# main.net
KiCad netlist of a schematic drawn in Altium Designer
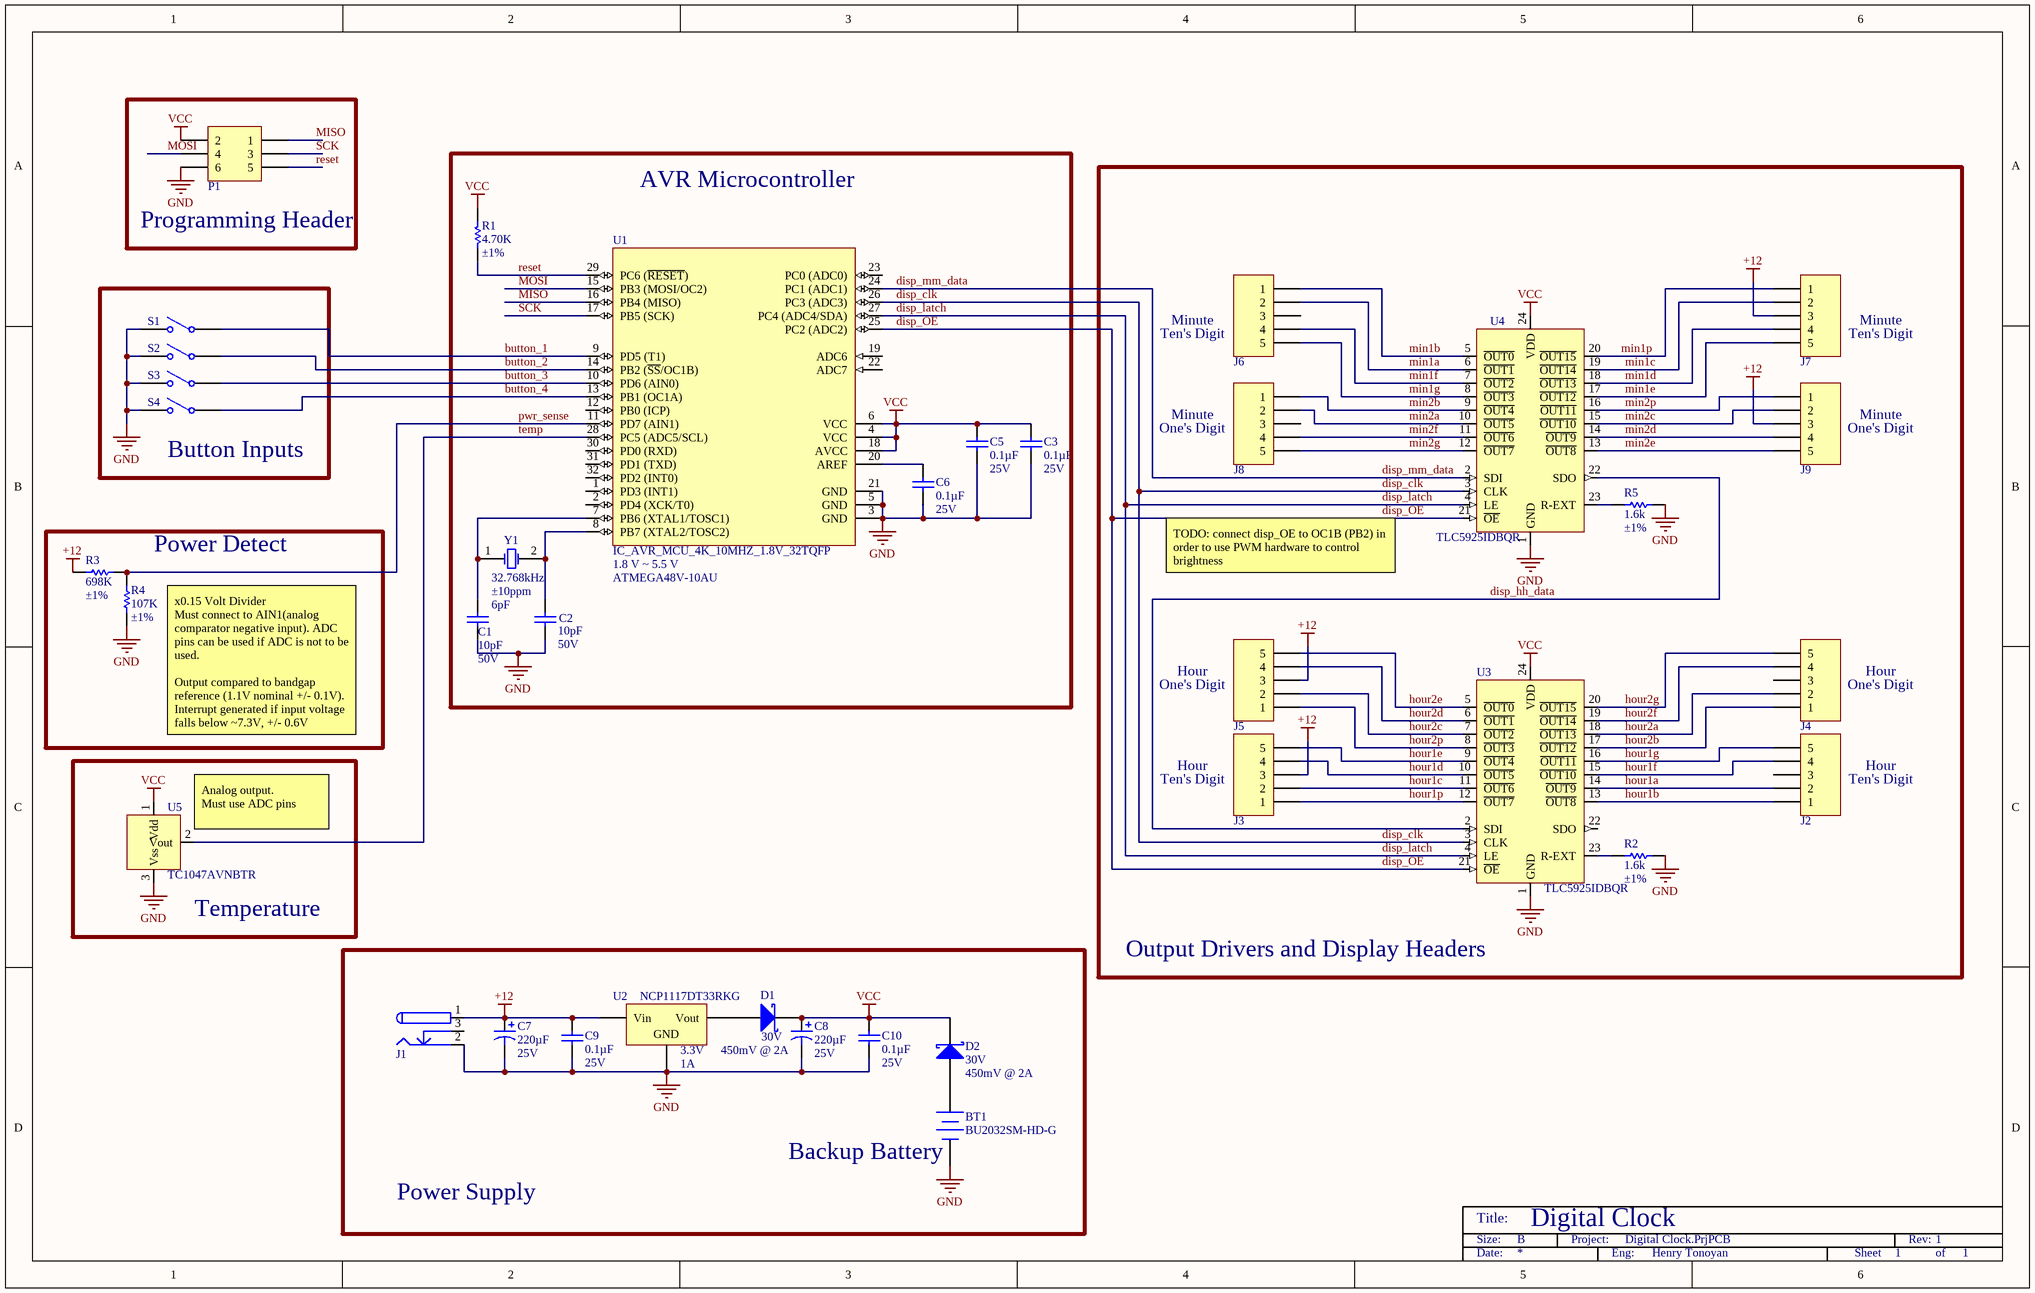
[diagram p0: main.SchDoc]

(export (version "E")
  (design (tool "Eeschema 10.0.6"))
  (components
    (comp (ref "BT1")
      (value "HOLDER COIN CELL 2032 SMD")
      (footprint "BU2032SM-HD-G")
      (fields
        (field (name "MANUFACTURER") "MPD (Memory Protection Devices)")
        (field (name "MANUFACTURER PART NUMBER") "BU2032SM-HD-G")
      )
      (libsource (lib "parts") (part "BU2032SM-HD-G"))
    )
    (comp (ref "C1")
      (value "CAP CER 10PF 50V 5% C0G 0603")
      (footprint "0603")
      (fields
        (field (name "MANUFACTURER") "Murata Electronics North America")
        (field (name "MANUFACTURER PART NUMBER") "GRM1885C1H100JA01D")
        (field (name "TOLERANCE") "±5%")
        (field (name "CAPACITANCE") "10pF")
        (field (name "VOLTAGE - RATED") "50V")
      )
      (libsource (lib "parts") (part "CAP_CER_10PF_50V_5%_C0G_0603"))
    )
    (comp (ref "C2")
      (value "CAP CER 10PF 50V 5% C0G 0603")
      (footprint "0603")
      (fields
        (field (name "MANUFACTURER") "Murata Electronics North America")
        (field (name "MANUFACTURER PART NUMBER") "GRM1885C1H100JA01D")
        (field (name "TOLERANCE") "±5%")
        (field (name "CAPACITANCE") "10pF")
        (field (name "VOLTAGE - RATED") "50V")
      )
      (libsource (lib "parts") (part "CAP_CER_10PF_50V_5%_C0G_0603"))
    )
    (comp (ref "C3")
      (value "CAP CER .10UF 25V X7R 10% 0603")
      (footprint "0603")
      (fields
        (field (name "MANUFACTURER") "TDK Corporation")
        (field (name "MANUFACTURER PART NUMBER") "C1608X7R1E104K")
        (field (name "TOLERANCE") "±10%")
        (field (name "CAPACITANCE") "0.1µF")
        (field (name "VOLTAGE - RATED") "25V")
      )
      (libsource (lib "parts") (part "CAP_CER_.10UF_25V_X7R_10%_0603_1"))
    )
    (comp (ref "C5")
      (value "CAP CER .10UF 25V X7R 10% 0603")
      (footprint "0603")
      (fields
        (field (name "MANUFACTURER") "TDK Corporation")
        (field (name "MANUFACTURER PART NUMBER") "C1608X7R1E104K")
        (field (name "TOLERANCE") "±10%")
        (field (name "CAPACITANCE") "0.1µF")
        (field (name "VOLTAGE - RATED") "25V")
      )
      (libsource (lib "parts") (part "CAP_CER_.10UF_25V_X7R_10%_0603_1"))
    )
    (comp (ref "C6")
      (value "CAP CER .10UF 25V X7R 10% 0603")
      (footprint "0603")
      (fields
        (field (name "MANUFACTURER") "TDK Corporation")
        (field (name "MANUFACTURER PART NUMBER") "C1608X7R1E104K")
        (field (name "TOLERANCE") "±10%")
        (field (name "CAPACITANCE") "0.1µF")
        (field (name "VOLTAGE - RATED") "25V")
      )
      (libsource (lib "parts") (part "CAP_CER_.10UF_25V_X7R_10%_0603_1"))
    )
    (comp (ref "C7")
      (value "CAP ALUM 220UF 25V 20% SMD")
      (footprint "CAP AVE227M25F24T-F")
      (fields
        (field (name "MANUFACTURER") "Cornell Dubilier Electronics (CDE)")
        (field (name "MANUFACTURER PART NUMBER") "AVE227M25F24T-F")
        (field (name "TOLERANCE") "±20%")
        (field (name "CAPACITANCE") "220µF")
        (field (name "VOLTAGE RATING") "25V")
      )
      (libsource (lib "parts") (part "CAP_ALUM_220UF_25V_20%_SMD"))
    )
    (comp (ref "C8")
      (value "CAP ALUM 220UF 25V 20% SMD")
      (footprint "CAP AVE227M25F24T-F")
      (fields
        (field (name "MANUFACTURER") "Cornell Dubilier Electronics (CDE)")
        (field (name "MANUFACTURER PART NUMBER") "AVE227M25F24T-F")
        (field (name "TOLERANCE") "±20%")
        (field (name "CAPACITANCE") "220µF")
        (field (name "VOLTAGE RATING") "25V")
      )
      (libsource (lib "parts") (part "CAP_ALUM_220UF_25V_20%_SMD"))
    )
    (comp (ref "C9")
      (value "CAP CER .10UF 25V X7R 10% 0603")
      (footprint "0603")
      (fields
        (field (name "MANUFACTURER") "TDK Corporation")
        (field (name "MANUFACTURER PART NUMBER") "C1608X7R1E104K")
        (field (name "TOLERANCE") "±10%")
        (field (name "CAPACITANCE") "0.1µF")
        (field (name "VOLTAGE - RATED") "25V")
      )
      (libsource (lib "parts") (part "CAP_CER_.10UF_25V_X7R_10%_0603_1"))
    )
    (comp (ref "C10")
      (value "CAP CER .10UF 25V X7R 10% 0603")
      (footprint "0603")
      (fields
        (field (name "MANUFACTURER") "TDK Corporation")
        (field (name "MANUFACTURER PART NUMBER") "C1608X7R1E104K")
        (field (name "TOLERANCE") "±10%")
        (field (name "CAPACITANCE") "0.1µF")
        (field (name "VOLTAGE - RATED") "25V")
      )
      (libsource (lib "parts") (part "CAP_CER_.10UF_25V_X7R_10%_0603_1"))
    )
    (comp (ref "D1")
      (value "DIODE_SCHOTTKY_30V_2A_SMB")
      (footprint "DSO-C2/X2.3")
      (description "DIODE SCHOTTKY 30V 2A SMB")
      (fields
        (field (name "MANUFACTURER") "STMicroelectronics")
        (field (name "MANUFACTURER PART NUMBER") "STPS2L30UF")
        (field (name "VOLTAGE - DC REVERSE (VR) (MAX)") "30V")
        (field (name "VOLTAGE - FORWARD (VF) (MAX) @ IF") "450mV @ 2A")
      )
      (libsource (lib "parts") (part "DIODE_SCHOTTKY_30V_2A_SMB"))
    )
    (comp (ref "D2")
      (value "DIODE_SCHOTTKY_30V_2A_SMB")
      (footprint "DSO-C2/X2.3")
      (description "DIODE SCHOTTKY 30V 2A SMB")
      (fields
        (field (name "MANUFACTURER") "STMicroelectronics")
        (field (name "MANUFACTURER PART NUMBER") "STPS2L30UF")
        (field (name "VOLTAGE - DC REVERSE (VR) (MAX)") "30V")
        (field (name "VOLTAGE - FORWARD (VF) (MAX) @ IF") "450mV @ 2A")
      )
      (libsource (lib "parts") (part "DIODE_SCHOTTKY_30V_2A_SMB"))
    )
    (comp (ref "J1")
      (value "CONN_PWR2.0_SMT")
      (footprint "CONN_PWR2.0_SMT")
      (description "CONN PWR JACK 2.0X6.3MM SMT")
      (fields (field (name "MANUFACTURER") "CUI Inc") (field (name "MANUFACTURER PART NUMBER") "PJ-036A-SMT"))
      (libsource (lib "parts") (part "CONN_PWR2.0_SMT"))
    )
    (comp (ref "J2")
      (value "CONN_HEADER_VERT_5POS_.100_TIN")
      (footprint "CONN_HDR1X5")
      (description "CONN HEADER VERT 5POS .100 TIN")
      (fields
        (field (name "MANUFACTURER") "TE Connectivity")
        (field (name "MANUFACTURER PART NUMBER") "640454-5")
      )
      (libsource (lib "") (part "CONN_HEADER_VERT_5POS_.100_TIN_3"))
    )
    (comp (ref "J3")
      (value "CONN_HEADER_VERT_5POS_.100_TIN")
      (footprint "CONN_HDR1X5")
      (description "CONN HEADER VERT 5POS .100 TIN")
      (fields
        (field (name "MANUFACTURER") "TE Connectivity")
        (field (name "MANUFACTURER PART NUMBER") "640454-5")
      )
      (libsource (lib "") (part "CONN_HEADER_VERT_5POS_.100_TIN_1"))
    )
    (comp (ref "J4")
      (value "CONN_HEADER_VERT_5POS_.100_TIN")
      (footprint "CONN_HDR1X5")
      (description "CONN HEADER VERT 5POS .100 TIN")
      (fields
        (field (name "MANUFACTURER") "TE Connectivity")
        (field (name "MANUFACTURER PART NUMBER") "640454-5")
      )
      (libsource (lib "") (part "CONN_HEADER_VERT_5POS_.100_TIN_3"))
    )
    (comp (ref "J5")
      (value "CONN_HEADER_VERT_5POS_.100_TIN")
      (footprint "CONN_HDR1X5")
      (description "CONN HEADER VERT 5POS .100 TIN")
      (fields
        (field (name "MANUFACTURER") "TE Connectivity")
        (field (name "MANUFACTURER PART NUMBER") "640454-5")
      )
      (libsource (lib "") (part "CONN_HEADER_VERT_5POS_.100_TIN_1"))
    )
    (comp (ref "J6")
      (value "CONN_HEADER_VERT_5POS_.100_TIN")
      (footprint "CONN_HDR1X5")
      (description "CONN HEADER VERT 5POS .100 TIN")
      (fields
        (field (name "MANUFACTURER") "TE Connectivity")
        (field (name "MANUFACTURER PART NUMBER") "640454-5")
      )
      (libsource (lib "") (part "CONN_HEADER_VERT_5POS_.100_TIN_2"))
    )
    (comp (ref "J7")
      (value "CONN_HEADER_VERT_5POS_.100_TIN")
      (footprint "CONN_HDR1X5")
      (description "CONN HEADER VERT 5POS .100 TIN")
      (fields
        (field (name "MANUFACTURER") "TE Connectivity")
        (field (name "MANUFACTURER PART NUMBER") "640454-5")
      )
      (libsource (lib "parts") (part "CONN_HEADER_VERT_5POS_.100_TIN"))
    )
    (comp (ref "J8")
      (value "CONN_HEADER_VERT_5POS_.100_TIN")
      (footprint "CONN_HDR1X5")
      (description "CONN HEADER VERT 5POS .100 TIN")
      (fields
        (field (name "MANUFACTURER") "TE Connectivity")
        (field (name "MANUFACTURER PART NUMBER") "640454-5")
      )
      (libsource (lib "") (part "CONN_HEADER_VERT_5POS_.100_TIN_2"))
    )
    (comp (ref "J9")
      (value "CONN_HEADER_VERT_5POS_.100_TIN")
      (footprint "CONN_HDR1X5")
      (description "CONN HEADER VERT 5POS .100 TIN")
      (fields
        (field (name "MANUFACTURER") "TE Connectivity")
        (field (name "MANUFACTURER PART NUMBER") "640454-5")
      )
      (libsource (lib "parts") (part "CONN_HEADER_VERT_5POS_.100_TIN"))
    )
    (comp (ref "P1")
      (value "Header, 3-Pin, Dual row")
      (footprint "CONN_HDR_SMT_6_2R")
      (fields
        (field (name "MANUFACTURER") "Molex Connector Corporation")
        (field (name "MANUFACTURER PART NUMBER") "15-91-2060")
      )
      (libsource (lib "parts") (part "CONN_Header_0.100_6pos"))
    )
    (comp (ref "R1")
      (value "RES_4.70K_OHM_1/10W_1%_0603_SMD")
      (footprint "0603")
      (description "RES 4.70K OHM 1/10W 1% 0603 SMD")
      (fields
        (field (name "MANUFACTURER") "Panasonic Electronic Components")
        (field (name "MANUFACTURER PART NUMBER") "ERJ-3EKF4701V")
        (field (name "RESISTANCE (OHMS)") "4.70K")
        (field (name "TOLERANCE") "±1%")
      )
      (libsource (lib "parts") (part "RES_4.70K_OHM_1/10W_1%_0603_SMD"))
    )
    (comp (ref "R2")
      (value "RES_1.60K_OHM_1/10W_1%_0603_SMD")
      (footprint "0603")
      (description "RES 1.60K OHM 1/10W 1% 0603 SMD")
      (fields
        (field (name "MANUFACTURER") "Panasonic Electronic Components")
        (field (name "MANUFACTURER PART NUMBER") "ERJ-3EKF1601V")
        (field (name "RESISTANCE (OHMS)") "1.6k")
        (field (name "TOLERANCE") "±1%")
      )
      (libsource (lib "parts") (part "RES_1.60K_OHM_1/10W_1%_0603_SMD"))
    )
    (comp (ref "R3")
      (value "RES_698K_OHM_1/10W_1%_0603_SMD")
      (footprint "0603")
      (description "RES 698K OHM 1/10W 1% 0603 SMD")
      (fields
        (field (name "MANUFACTURER") "Panasonic Electronic Components")
        (field (name "MANUFACTURER PART NUMBER") "ERJ-3EKF6983V")
        (field (name "RESISTANCE (OHMS)") "698K")
        (field (name "TOLERANCE") "±1%")
      )
      (libsource (lib "parts") (part "RES_698K_OHM_1/10W_1%_0603_SMD"))
    )
    (comp (ref "R4")
      (value "RES_107K_OHM_1/10W_1%_0603_SMD")
      (footprint "0603")
      (description "RES 107K OHM 1/10W 1% 0603 SMD")
      (fields
        (field (name "MANUFACTURER") "Panasonic Electronic Components")
        (field (name "MANUFACTURER PART NUMBER") "ERJ-3EKF1073V")
        (field (name "RESISTANCE (OHMS)") "107K")
        (field (name "TOLERANCE") "±1%")
      )
      (libsource (lib "parts") (part "RES_107K_OHM_1/10W_1%_0603_SMD"))
    )
    (comp (ref "R5")
      (value "RES_1.60K_OHM_1/10W_1%_0603_SMD")
      (footprint "0603")
      (description "RES 1.60K OHM 1/10W 1% 0603 SMD")
      (fields
        (field (name "MANUFACTURER") "Panasonic Electronic Components")
        (field (name "MANUFACTURER PART NUMBER") "ERJ-3EKF1601V")
        (field (name "RESISTANCE (OHMS)") "1.6k")
        (field (name "TOLERANCE") "±1%")
      )
      (libsource (lib "parts") (part "RES_1.60K_OHM_1/10W_1%_0603_SMD"))
    )
    (comp (ref "S1")
      (value "SW_1571634-2")
      (footprint "1571634-2")
      (description "Single-Pole, Single-Throw Switch")
      (fields
        (field (name "MANUFACTURER") "TE Connectivity / Alcoswitch")
        (field (name "MANUFACTURER PART NUMBER") "1571634-2")
        (field (name "PUBLISHER") "Altium Limited")
      )
      (libsource (lib "parts") (part "SW_1571634-2"))
    )
    (comp (ref "S2")
      (value "SW_1571634-2")
      (footprint "1571634-2")
      (description "Single-Pole, Single-Throw Switch")
      (fields
        (field (name "MANUFACTURER") "TE Connectivity / Alcoswitch")
        (field (name "MANUFACTURER PART NUMBER") "1571634-2")
        (field (name "PUBLISHER") "Altium Limited")
      )
      (libsource (lib "parts") (part "SW_1571634-2"))
    )
    (comp (ref "S3")
      (value "SW_1571634-2")
      (footprint "1571634-2")
      (description "Single-Pole, Single-Throw Switch")
      (fields
        (field (name "MANUFACTURER") "TE Connectivity / Alcoswitch")
        (field (name "MANUFACTURER PART NUMBER") "1571634-2")
        (field (name "PUBLISHER") "Altium Limited")
      )
      (libsource (lib "parts") (part "SW_1571634-2"))
    )
    (comp (ref "S4")
      (value "SW_1571634-2")
      (footprint "1571634-2")
      (description "Single-Pole, Single-Throw Switch")
      (fields
        (field (name "MANUFACTURER") "TE Connectivity / Alcoswitch")
        (field (name "MANUFACTURER PART NUMBER") "1571634-2")
        (field (name "PUBLISHER") "Altium Limited")
      )
      (libsource (lib "parts") (part "SW_1571634-2"))
    )
    (comp (ref "U1")
      (value "IC_AVR_MCU_4K_10MHZ_1.8V_32TQFP")
      (footprint "32A_N")
      (description "IC AVR MCU 4K 10MHZ 1.8V 32TQFP")
      (fields
        (field (name "MANUFACTURER") "Atmel")
        (field (name "VOLTAGE - SUPPLY (VCC/VDD)") "1.8 V ~ 5.5 V")
        (field (name "MANUFACTURER PART NUMBER") "ATMEGA48V-10AU")
      )
      (libsource (lib "parts") (part "IC_AVR_MCU_4K_10MHZ_1.8V_32TQFP"))
    )
    (comp (ref "U2")
      (value "IC_REG_LDO_3.3V_DPAK")
      (footprint "DPAK")
      (description "IC REG LDO 3.3V DPAK")
      (fields
        (field (name "MANUFACTURER") "ON Semiconductor")
        (field (name "MANUFACTURER PART NUMBER") "NCP1117DT33RKG")
        (field (name "VOLTAGE - OUTPUT") "3.3V")
        (field (name "CURRENT - OUTPUT") "1A")
      )
      (libsource (lib "parts") (part "IC_REG_LDO_3.3V_DPAK"))
    )
    (comp (ref "U3")
      (value "IC_LED_DRIVER_LINEAR_24-QSOP")
      (footprint "SOP24")
      (description "IC LED DRIVER LINEAR 24-QSOP")
      (fields
        (field (name "MANUFACTURER") "Texas Instruments")
        (field (name "MANUFACTURER PART NUMBER") "TLC5925IDBQR")
      )
      (libsource (lib "parts") (part "IC_LED_DRIVER_LINEAR_24-QSOP"))
    )
    (comp (ref "U4")
      (value "IC_LED_DRIVER_LINEAR_24-QSOP")
      (footprint "SOP24")
      (description "IC LED DRIVER LINEAR 24-QSOP")
      (fields
        (field (name "MANUFACTURER") "Texas Instruments")
        (field (name "MANUFACTURER PART NUMBER") "TLC5925IDBQR")
      )
      (libsource (lib "parts") (part "IC_LED_DRIVER_LINEAR_24-QSOP"))
    )
    (comp (ref "U5")
      (value "Temperature Sensor")
      (footprint "SOT23-3N")
      (description "IC TEMP-VOLT CONV PREC SOT-23B")
      (fields
        (field (name "MANUFACTURER") "Microchip Technology")
        (field (name "MANUFACTURER PART NUMBER") "TC1047AVNBTR")
      )
      (libsource (lib "parts") (part "IC_TEMP-VOLT_CONV_PREC_SOT-23B"))
    )
    (comp (ref "Y1")
      (value "CRYSTAL_32.768_KHZ_6.0 PF_SMD")
      (footprint "ABS25")
      (description "CRYSTAL 32.768 KHZ 6.0 PF SMD")
      (fields
        (field (name "MANUFACTURER") "Abracon Corporation")
        (field (name "MANUFACTURER PART NUMBER") "ABS25-32.768KHZ-6-1-T")
        (field (name "FREQUENCY") "32.768kHz")
        (field (name "FREQUENCY TOLERANCE") "±10ppm")
        (field (name "LOAD CAPACITANCE") "6pF")
      )
      (libsource (lib "parts") (part "CRYSTAL_32.768_KHZ_6.0 PF_SMD"))
    )
  )
  (nets
    (net (code "1") (name "+12") (class "Default")
      (node (ref "C7") (pin "1") (pinfunction "1_1") (pintype "passive"))
      (node (ref "C9") (pin "2") (pinfunction "2_2") (pintype "passive"))
      (node (ref "J1") (pin "1") (pinfunction "1_1") (pintype "power_in"))
      (node (ref "J3") (pin "3") (pinfunction "3_3") (pintype "passive"))
      (node (ref "J5") (pin "3") (pinfunction "3_3") (pintype "passive"))
      (node (ref "J7") (pin "3") (pinfunction "3_3") (pintype "passive"))
      (node (ref "J9") (pin "3") (pinfunction "3_3") (pintype "passive"))
      (node (ref "R3") (pin "1") (pinfunction "1_1") (pintype "passive"))
      (node (ref "U2") (pin "1") (pinfunction "Vin_1") (pintype "passive"))
    )
    (net (code "2") (name "/MISO") (class "Default")
      (node (ref "P1") (pin "1") (pinfunction "1_1") (pintype "passive"))
      (node (ref "U1") (pin "16") (pinfunction "PB4_(MISO)_16") (pintype "bidirectional"))
    )
    (net (code "3") (name "/MOSI") (class "Default")
      (node (ref "P1") (pin "4") (pinfunction "4_4") (pintype "passive"))
      (node (ref "U1") (pin "15") (pinfunction "PB3_(MOSI/OC2)_15") (pintype "bidirectional"))
    )
    (net (code "4") (name "/SCK") (class "Default")
      (node (ref "P1") (pin "3") (pinfunction "3_3") (pintype "passive"))
      (node (ref "U1") (pin "17") (pinfunction "PB5_(SCK)_17") (pintype "bidirectional"))
    )
    (net (code "5") (name "/button_1") (class "Default")
      (node (ref "S1") (pin "1") (pinfunction "COMMON_1") (pintype "passive"))
      (node (ref "U1") (pin "9") (pinfunction "PD5_(T1)_9") (pintype "bidirectional"))
    )
    (net (code "6") (name "/button_2") (class "Default")
      (node (ref "S2") (pin "1") (pinfunction "COMMON_1") (pintype "passive"))
      (node (ref "U1") (pin "14") (pinfunction "PB2_(~{SS}/OC1B)_14") (pintype "bidirectional"))
    )
    (net (code "7") (name "/button_3") (class "Default")
      (node (ref "S3") (pin "1") (pinfunction "COMMON_1") (pintype "passive"))
      (node (ref "U1") (pin "10") (pinfunction "PD6_(AIN0)_10") (pintype "bidirectional"))
    )
    (net (code "8") (name "/button_4") (class "Default")
      (node (ref "S4") (pin "1") (pinfunction "COMMON_1") (pintype "passive"))
      (node (ref "U1") (pin "13") (pinfunction "PB1_(OC1A)_13") (pintype "bidirectional"))
    )
    (net (code "9") (name "/disp_clk") (class "Default")
      (node (ref "U1") (pin "26") (pinfunction "PC3_(ADC3)_26") (pintype "bidirectional"))
      (node (ref "U3") (pin "3") (pinfunction "CLK_3") (pintype "input"))
      (node (ref "U4") (pin "3") (pinfunction "CLK_3") (pintype "input"))
    )
    (net (code "10") (name "/disp_hh_data") (class "Default")
      (node (ref "U3") (pin "2") (pinfunction "SDI_2") (pintype "input"))
      (node (ref "U4") (pin "22") (pinfunction "SDO_22") (pintype "output"))
    )
    (net (code "11") (name "/disp_latch") (class "Default")
      (node (ref "U1") (pin "27") (pinfunction "PC4_(ADC4/SDA)_27") (pintype "bidirectional"))
      (node (ref "U3") (pin "4") (pinfunction "LE_4") (pintype "input"))
      (node (ref "U4") (pin "4") (pinfunction "LE_4") (pintype "input"))
    )
    (net (code "12") (name "/disp_mm_data") (class "Default")
      (node (ref "U1") (pin "24") (pinfunction "PC1_(ADC1)_24") (pintype "bidirectional"))
      (node (ref "U4") (pin "2") (pinfunction "SDI_2") (pintype "input"))
    )
    (net (code "13") (name "/disp_~{OE}") (class "Default")
      (node (ref "U1") (pin "25") (pinfunction "PC2_(ADC2)_25") (pintype "bidirectional"))
      (node (ref "U3") (pin "21") (pinfunction "~{OE}_21") (pintype "input"))
      (node (ref "U4") (pin "21") (pinfunction "~{OE}_21") (pintype "input"))
    )
    (net (code "14") (name "/hour1a") (class "Default")
      (node (ref "J2") (pin "2") (pinfunction "2_2") (pintype "passive"))
      (node (ref "U3") (pin "14") (pinfunction "~{OUT9}_14") (pintype "passive"))
    )
    (net (code "15") (name "/hour1b") (class "Default")
      (node (ref "J2") (pin "1") (pinfunction "1_1") (pintype "passive"))
      (node (ref "U3") (pin "13") (pinfunction "~{OUT8}_13") (pintype "passive"))
    )
    (net (code "16") (name "/hour1c") (class "Default")
      (node (ref "J3") (pin "2") (pinfunction "2_2") (pintype "passive"))
      (node (ref "U3") (pin "11") (pinfunction "~{OUT6}_11") (pintype "passive"))
    )
    (net (code "17") (name "/hour1d") (class "Default")
      (node (ref "J3") (pin "4") (pinfunction "4_4") (pintype "passive"))
      (node (ref "U3") (pin "10") (pinfunction "~{OUT5}_10") (pintype "passive"))
    )
    (net (code "18") (name "/hour1e") (class "Default")
      (node (ref "J3") (pin "5") (pinfunction "5_5") (pintype "passive"))
      (node (ref "U3") (pin "9") (pinfunction "~{OUT4}_9") (pintype "passive"))
    )
    (net (code "19") (name "/hour1f") (class "Default")
      (node (ref "J2") (pin "4") (pinfunction "4_4") (pintype "passive"))
      (node (ref "U3") (pin "15") (pinfunction "~{OUT10}_15") (pintype "passive"))
    )
    (net (code "20") (name "/hour1g") (class "Default")
      (node (ref "J2") (pin "5") (pinfunction "5_5") (pintype "passive"))
      (node (ref "U3") (pin "16") (pinfunction "~{OUT11}_16") (pintype "passive"))
    )
    (net (code "21") (name "/hour1p") (class "Default")
      (node (ref "J3") (pin "1") (pinfunction "1_1") (pintype "passive"))
      (node (ref "U3") (pin "12") (pinfunction "~{OUT7}_12") (pintype "passive"))
    )
    (net (code "22") (name "/hour2a") (class "Default")
      (node (ref "J4") (pin "2") (pinfunction "2_2") (pintype "passive"))
      (node (ref "U3") (pin "18") (pinfunction "~{OUT13}_18") (pintype "passive"))
    )
    (net (code "23") (name "/hour2b") (class "Default")
      (node (ref "J4") (pin "1") (pinfunction "1_1") (pintype "passive"))
      (node (ref "U3") (pin "17") (pinfunction "~{OUT12}_17") (pintype "passive"))
    )
    (net (code "24") (name "/hour2c") (class "Default")
      (node (ref "J5") (pin "2") (pinfunction "2_2") (pintype "passive"))
      (node (ref "U3") (pin "7") (pinfunction "~{OUT2}_7") (pintype "passive"))
    )
    (net (code "25") (name "/hour2d") (class "Default")
      (node (ref "J5") (pin "4") (pinfunction "4_4") (pintype "passive"))
      (node (ref "U3") (pin "6") (pinfunction "~{OUT1}_6") (pintype "passive"))
    )
    (net (code "26") (name "/hour2e") (class "Default")
      (node (ref "J5") (pin "5") (pinfunction "5_5") (pintype "passive"))
      (node (ref "U3") (pin "5") (pinfunction "~{OUT0}_5") (pintype "passive"))
    )
    (net (code "27") (name "/hour2f") (class "Default")
      (node (ref "J4") (pin "4") (pinfunction "4_4") (pintype "passive"))
      (node (ref "U3") (pin "19") (pinfunction "~{OUT14}_19") (pintype "passive"))
    )
    (net (code "28") (name "/hour2g") (class "Default")
      (node (ref "J4") (pin "5") (pinfunction "5_5") (pintype "passive"))
      (node (ref "U3") (pin "20") (pinfunction "~{OUT15}_20") (pintype "passive"))
    )
    (net (code "29") (name "/hour2p") (class "Default")
      (node (ref "J5") (pin "1") (pinfunction "1_1") (pintype "passive"))
      (node (ref "U3") (pin "8") (pinfunction "~{OUT3}_8") (pintype "passive"))
    )
    (net (code "30") (name "/min1a") (class "Default")
      (node (ref "J6") (pin "2") (pinfunction "2_2") (pintype "passive"))
      (node (ref "U4") (pin "6") (pinfunction "~{OUT1}_6") (pintype "passive"))
    )
    (net (code "31") (name "/min1b") (class "Default")
      (node (ref "J6") (pin "1") (pinfunction "1_1") (pintype "passive"))
      (node (ref "U4") (pin "5") (pinfunction "~{OUT0}_5") (pintype "passive"))
    )
    (net (code "32") (name "/min1c") (class "Default")
      (node (ref "J7") (pin "2") (pinfunction "2_2") (pintype "passive"))
      (node (ref "U4") (pin "19") (pinfunction "~{OUT14}_19") (pintype "passive"))
    )
    (net (code "33") (name "/min1d") (class "Default")
      (node (ref "J7") (pin "4") (pinfunction "4_4") (pintype "passive"))
      (node (ref "U4") (pin "18") (pinfunction "~{OUT13}_18") (pintype "passive"))
    )
    (net (code "34") (name "/min1e") (class "Default")
      (node (ref "J7") (pin "5") (pinfunction "5_5") (pintype "passive"))
      (node (ref "U4") (pin "17") (pinfunction "~{OUT12}_17") (pintype "passive"))
    )
    (net (code "35") (name "/min1f") (class "Default")
      (node (ref "J6") (pin "4") (pinfunction "4_4") (pintype "passive"))
      (node (ref "U4") (pin "7") (pinfunction "~{OUT2}_7") (pintype "passive"))
    )
    (net (code "36") (name "/min1g") (class "Default")
      (node (ref "J6") (pin "5") (pinfunction "5_5") (pintype "passive"))
      (node (ref "U4") (pin "8") (pinfunction "~{OUT3}_8") (pintype "passive"))
    )
    (net (code "37") (name "/min1p") (class "Default")
      (node (ref "J7") (pin "1") (pinfunction "1_1") (pintype "passive"))
      (node (ref "U4") (pin "20") (pinfunction "~{OUT15}_20") (pintype "passive"))
    )
    (net (code "38") (name "/min2a") (class "Default")
      (node (ref "J8") (pin "2") (pinfunction "2_2") (pintype "passive"))
      (node (ref "U4") (pin "10") (pinfunction "~{OUT5}_10") (pintype "passive"))
    )
    (net (code "39") (name "/min2b") (class "Default")
      (node (ref "J8") (pin "1") (pinfunction "1_1") (pintype "passive"))
      (node (ref "U4") (pin "9") (pinfunction "~{OUT4}_9") (pintype "passive"))
    )
    (net (code "40") (name "/min2c") (class "Default")
      (node (ref "J9") (pin "2") (pinfunction "2_2") (pintype "passive"))
      (node (ref "U4") (pin "15") (pinfunction "~{OUT10}_15") (pintype "passive"))
    )
    (net (code "41") (name "/min2d") (class "Default")
      (node (ref "J9") (pin "4") (pinfunction "4_4") (pintype "passive"))
      (node (ref "U4") (pin "14") (pinfunction "~{OUT9}_14") (pintype "passive"))
    )
    (net (code "42") (name "/min2e") (class "Default")
      (node (ref "J9") (pin "5") (pinfunction "5_5") (pintype "passive"))
      (node (ref "U4") (pin "13") (pinfunction "~{OUT8}_13") (pintype "passive"))
    )
    (net (code "43") (name "/min2f") (class "Default")
      (node (ref "J8") (pin "4") (pinfunction "4_4") (pintype "passive"))
      (node (ref "U4") (pin "11") (pinfunction "~{OUT6}_11") (pintype "passive"))
    )
    (net (code "44") (name "/min2g") (class "Default")
      (node (ref "J8") (pin "5") (pinfunction "5_5") (pintype "passive"))
      (node (ref "U4") (pin "12") (pinfunction "~{OUT7}_12") (pintype "passive"))
    )
    (net (code "45") (name "/min2p") (class "Default")
      (node (ref "J9") (pin "1") (pinfunction "1_1") (pintype "passive"))
      (node (ref "U4") (pin "16") (pinfunction "~{OUT11}_16") (pintype "passive"))
    )
    (net (code "46") (name "/pwr_sense") (class "Default")
      (node (ref "R3") (pin "2") (pinfunction "2_2") (pintype "passive"))
      (node (ref "R4") (pin "2") (pinfunction "2_2") (pintype "passive"))
      (node (ref "U1") (pin "11") (pinfunction "PD7_(AIN1)_11") (pintype "bidirectional"))
    )
    (net (code "47") (name "/reset") (class "Default")
      (node (ref "P1") (pin "5") (pinfunction "5_5") (pintype "passive"))
      (node (ref "R1") (pin "1") (pinfunction "1_1") (pintype "passive"))
      (node (ref "U1") (pin "29") (pinfunction "PC6_(~{RESET})_29") (pintype "bidirectional"))
    )
    (net (code "48") (name "/temp") (class "Default")
      (node (ref "U1") (pin "28") (pinfunction "PC5_(ADC5/SCL)_28") (pintype "bidirectional"))
      (node (ref "U5") (pin "2") (pinfunction "Vout_2") (pintype "passive"))
    )
    (net (code "49") (name "GND") (class "Default")
      (node (ref "BT1") (pin "2") (pinfunction "-_2") (pintype "passive"))
      (node (ref "C1") (pin "1") (pinfunction "1_1") (pintype "passive"))
      (node (ref "C10") (pin "1") (pinfunction "1_1") (pintype "passive"))
      (node (ref "C2") (pin "1") (pinfunction "1_1") (pintype "passive"))
      (node (ref "C3") (pin "2") (pinfunction "2_2") (pintype "passive"))
      (node (ref "C5") (pin "2") (pinfunction "2_2") (pintype "passive"))
      (node (ref "C6") (pin "2") (pinfunction "2_2") (pintype "passive"))
      (node (ref "C7") (pin "2") (pinfunction "2_2") (pintype "passive"))
      (node (ref "C8") (pin "2") (pinfunction "2_2") (pintype "passive"))
      (node (ref "C9") (pin "1") (pinfunction "1_1") (pintype "passive"))
      (node (ref "J1") (pin "2") (pinfunction "2_2") (pintype "power_in"))
      (node (ref "P1") (pin "6") (pinfunction "6_6") (pintype "passive"))
      (node (ref "R2") (pin "2") (pinfunction "2_2") (pintype "passive"))
      (node (ref "R4") (pin "1") (pinfunction "1_1") (pintype "passive"))
      (node (ref "R5") (pin "2") (pinfunction "2_2") (pintype "passive"))
      (node (ref "S1") (pin "2") (pinfunction "NO_2") (pintype "passive"))
      (node (ref "S2") (pin "2") (pinfunction "NO_2") (pintype "passive"))
      (node (ref "S3") (pin "2") (pinfunction "NO_2") (pintype "passive"))
      (node (ref "S4") (pin "2") (pinfunction "NO_2") (pintype "passive"))
      (node (ref "U1") (pin "21") (pinfunction "GND_21") (pintype "power_in"))
      (node (ref "U1") (pin "3") (pinfunction "GND_3") (pintype "power_in"))
      (node (ref "U1") (pin "5") (pinfunction "GND_5") (pintype "power_in"))
      (node (ref "U2") (pin "2") (pinfunction "GND_2") (pintype "passive"))
      (node (ref "U3") (pin "1") (pinfunction "GND_1") (pintype "passive"))
      (node (ref "U4") (pin "1") (pinfunction "GND_1") (pintype "passive"))
      (node (ref "U5") (pin "3") (pinfunction "Vss_3") (pintype "passive"))
    )
    (net (code "50") (name "Net-(BT1-+)") (class "Default")
      (node (ref "BT1") (pin "1") (pinfunction "+_1") (pintype "passive"))
      (node (ref "D2") (pin "1") (pinfunction "A_1") (pintype "passive"))
    )
    (net (code "51") (name "Net-(D1-A)") (class "Default")
      (node (ref "D1") (pin "1") (pinfunction "A_1") (pintype "passive"))
      (node (ref "U2") (pin "3") (pinfunction "Vout_3") (pintype "passive"))
    )
    (net (code "52") (name "Net-(U1-AREF)") (class "Default")
      (node (ref "C6") (pin "1") (pinfunction "1_1") (pintype "passive"))
      (node (ref "U1") (pin "20") (pinfunction "AREF_20") (pintype "passive"))
    )
    (net (code "53") (name "Net-(U1-PB6_(XTAL1{slash}TOSC1))") (class "Default")
      (node (ref "C1") (pin "2") (pinfunction "2_2") (pintype "passive"))
      (node (ref "U1") (pin "7") (pinfunction "PB6_(XTAL1/TOSC1)_7") (pintype "bidirectional"))
      (node (ref "Y1") (pin "1") (pinfunction "OSC1_1") (pintype "passive"))
    )
    (net (code "54") (name "Net-(U1-PB7_(XTAL2{slash}TOSC2))") (class "Default")
      (node (ref "C2") (pin "2") (pinfunction "2_2") (pintype "passive"))
      (node (ref "U1") (pin "8") (pinfunction "PB7_(XTAL2/TOSC2)_8") (pintype "bidirectional"))
      (node (ref "Y1") (pin "2") (pinfunction "OSC2_2") (pintype "passive"))
    )
    (net (code "55") (name "Net-(U3-R-EXT)") (class "Default")
      (node (ref "R2") (pin "1") (pinfunction "1_1") (pintype "passive"))
      (node (ref "U3") (pin "23") (pinfunction "R-EXT_23") (pintype "passive"))
    )
    (net (code "56") (name "Net-(U4-R-EXT)") (class "Default")
      (node (ref "R5") (pin "1") (pinfunction "1_1") (pintype "passive"))
      (node (ref "U4") (pin "23") (pinfunction "R-EXT_23") (pintype "passive"))
    )
    (net (code "57") (name "VCC") (class "Default")
      (node (ref "C10") (pin "2") (pinfunction "2_2") (pintype "passive"))
      (node (ref "C3") (pin "1") (pinfunction "1_1") (pintype "passive"))
      (node (ref "C5") (pin "1") (pinfunction "1_1") (pintype "passive"))
      (node (ref "C8") (pin "1") (pinfunction "1_1") (pintype "passive"))
      (node (ref "D1") (pin "2") (pinfunction "K_2") (pintype "passive"))
      (node (ref "D2") (pin "2") (pinfunction "K_2") (pintype "passive"))
      (node (ref "P1") (pin "2") (pinfunction "2_2") (pintype "passive"))
      (node (ref "R1") (pin "2") (pinfunction "2_2") (pintype "passive"))
      (node (ref "U1") (pin "18") (pinfunction "AVCC_18") (pintype "power_in"))
      (node (ref "U1") (pin "4") (pinfunction "VCC_4") (pintype "power_in"))
      (node (ref "U1") (pin "6") (pinfunction "VCC_6") (pintype "power_in"))
      (node (ref "U3") (pin "24") (pinfunction "VDD_24") (pintype "passive"))
      (node (ref "U4") (pin "24") (pinfunction "VDD_24") (pintype "passive"))
      (node (ref "U5") (pin "1") (pinfunction "Vdd_1") (pintype "passive"))
    )
    (net (code "58") (name "unconnected-(J1-Pad3)") (class "Default")
      (node (ref "J1") (pin "3") (pinfunction "3_3") (pintype "power_in"))
    )
    (net (code "59") (name "unconnected-(J2-Pad3)") (class "Default")
      (node (ref "J2") (pin "3") (pinfunction "3_3") (pintype "passive"))
    )
    (net (code "60") (name "unconnected-(J4-Pad3)") (class "Default")
      (node (ref "J4") (pin "3") (pinfunction "3_3") (pintype "passive"))
    )
    (net (code "61") (name "unconnected-(J6-Pad3)") (class "Default")
      (node (ref "J6") (pin "3") (pinfunction "3_3") (pintype "passive"))
    )
    (net (code "62") (name "unconnected-(J8-Pad3)") (class "Default")
      (node (ref "J8") (pin "3") (pinfunction "3_3") (pintype "passive"))
    )
    (net (code "63") (name "unconnected-(U1-ADC6-Pad19)") (class "Default")
      (node (ref "U1") (pin "19") (pinfunction "ADC6_19") (pintype "input"))
    )
    (net (code "64") (name "unconnected-(U1-ADC7-Pad22)") (class "Default")
      (node (ref "U1") (pin "22") (pinfunction "ADC7_22") (pintype "input"))
    )
    (net (code "65") (name "unconnected-(U1-PB0_(ICP)-Pad12)") (class "Default")
      (node (ref "U1") (pin "12") (pinfunction "PB0_(ICP)_12") (pintype "bidirectional"))
    )
    (net (code "66") (name "unconnected-(U1-PC0_(ADC0)-Pad23)") (class "Default")
      (node (ref "U1") (pin "23") (pinfunction "PC0_(ADC0)_23") (pintype "bidirectional"))
    )
    (net (code "67") (name "unconnected-(U1-PD0_(RXD)-Pad30)") (class "Default")
      (node (ref "U1") (pin "30") (pinfunction "PD0_(RXD)_30") (pintype "bidirectional"))
    )
    (net (code "68") (name "unconnected-(U1-PD1_(TXD)-Pad31)") (class "Default")
      (node (ref "U1") (pin "31") (pinfunction "PD1_(TXD)_31") (pintype "bidirectional"))
    )
    (net (code "69") (name "unconnected-(U1-PD2_(INT0)-Pad32)") (class "Default")
      (node (ref "U1") (pin "32") (pinfunction "PD2_(INT0)_32") (pintype "bidirectional"))
    )
    (net (code "70") (name "unconnected-(U1-PD3_(INT1)-Pad1)") (class "Default")
      (node (ref "U1") (pin "1") (pinfunction "PD3_(INT1)_1") (pintype "bidirectional"))
    )
    (net (code "71") (name "unconnected-(U1-PD4_(XCK{slash}T0)-Pad2)") (class "Default")
      (node (ref "U1") (pin "2") (pinfunction "PD4_(XCK/T0)_2") (pintype "bidirectional"))
    )
    (net (code "72") (name "unconnected-(U3-SDO-Pad22)") (class "Default")
      (node (ref "U3") (pin "22") (pinfunction "SDO_22") (pintype "output"))
    )
  )
)
